# ToF_Bottom.net
KiCad netlist of a schematic drawn in Altium Designer
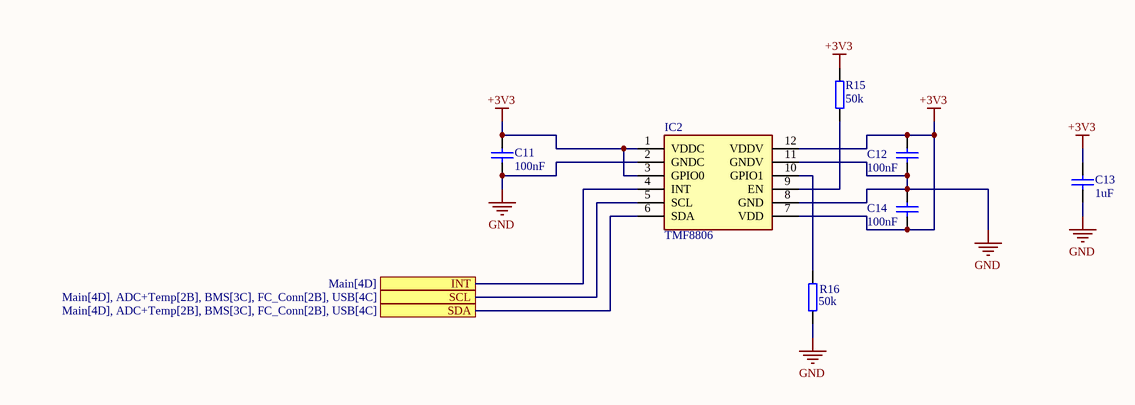
[diagram p0: ToF_Bottom.SchDoc]

(export (version "E")
  (design (tool "Eeschema 10.0.6"))
  (components
    (comp (ref "C11")
      (value "100nF")
      (footprint "CAP0402")
      (fields
        (field (name "VOLTAGE") "50V")
        (field (name "MANUFACTURER_PART_NUMBER") "GRM155R71H104ME14D")
        (field (name "Comment") "Cap0402")
      )
      (libsource (lib "capacitorsSMD") (part "Cap0402"))
    )
    (comp (ref "C12")
      (value "100nF")
      (footprint "CAP0402")
      (fields
        (field (name "VOLTAGE") "50V")
        (field (name "MANUFACTURER_PART_NUMBER") "GRM155R71H104ME14D")
        (field (name "Comment") "Cap0402")
      )
      (libsource (lib "capacitorsSMD") (part "Cap0402"))
    )
    (comp (ref "C13")
      (value "1uF")
      (footprint "CAP0603")
      (fields
        (field (name "VOLTAGE") "25V")
        (field (name "MANUFACTURER_PART_NUMBER") "GRT188R61H105KE13D")
        (field (name "Comment") "Cap0603")
      )
      (libsource (lib "capacitorsSMD") (part "Cap0603"))
    )
    (comp (ref "C14")
      (value "100nF")
      (footprint "CAP0402")
      (fields
        (field (name "VOLTAGE") "50V")
        (field (name "MANUFACTURER_PART_NUMBER") "GRM155R71H104ME14D")
        (field (name "Comment") "Cap0402")
      )
      (libsource (lib "capacitorsSMD") (part "Cap0402"))
    )
    (comp (ref "IC2")
      (value "TMF8806")
      (footprint "SamacSys:TMF88051B")
      (description "Integrated Circuit")
      (fields
        (field (name "MANUFACTURER_PART_NUMBER") "TMF8805-1B")
        (field (name "MOUSER PART NUMBER") "985-TMF8805-1B")
      )
      (libsource (lib "*") (part "TMF8805-1B"))
    )
    (comp (ref "R15")
      (value "50k")
      (footprint "RES0402")
      (fields (field (name "MANUFACTURER_PART_NUMBER") "TNPW040249K9DEED") (field (name "Comment") "Res0402"))
      (libsource (lib "resistorSMD") (part "Res0402"))
    )
    (comp (ref "R16")
      (value "50k")
      (footprint "RES0402")
      (fields (field (name "MANUFACTURER_PART_NUMBER") "TNPW040249K9DEED") (field (name "Comment") "Res0402"))
      (libsource (lib "resistorSMD") (part "Res0402"))
    )
  )
  (nets
    (net (code "1") (name "+3V3") (class "Default")
      (node (ref "C11") (pin "2") (pinfunction "2_2") (pintype "passive"))
      (node (ref "C12") (pin "2") (pinfunction "2_2") (pintype "passive"))
      (node (ref "C13") (pin "2") (pinfunction "2_2") (pintype "passive"))
      (node (ref "C14") (pin "1") (pinfunction "1_1") (pintype "passive"))
      (node (ref "IC2") (pin "1") (pinfunction "VDDC_1") (pintype "passive"))
      (node (ref "IC2") (pin "12") (pinfunction "VDDV_12") (pintype "passive"))
      (node (ref "IC2") (pin "3") (pinfunction "GPIO0_3") (pintype "passive"))
      (node (ref "IC2") (pin "7") (pinfunction "VDD_7") (pintype "passive"))
      (node (ref "R15") (pin "2") (pinfunction "2_2") (pintype "passive"))
    )
    (net (code "2") (name "/INT") (class "Default")
      (node (ref "IC2") (pin "4") (pinfunction "INT_4") (pintype "passive"))
    )
    (net (code "3") (name "/SCL") (class "Default")
      (node (ref "IC2") (pin "5") (pinfunction "SCL_5") (pintype "passive"))
    )
    (net (code "4") (name "/SDA") (class "Default")
      (node (ref "IC2") (pin "6") (pinfunction "SDA_6") (pintype "passive"))
    )
    (net (code "5") (name "GND") (class "Default")
      (node (ref "C11") (pin "1") (pinfunction "1_1") (pintype "passive"))
      (node (ref "C12") (pin "1") (pinfunction "1_1") (pintype "passive"))
      (node (ref "C13") (pin "1") (pinfunction "1_1") (pintype "passive"))
      (node (ref "C14") (pin "2") (pinfunction "2_2") (pintype "passive"))
      (node (ref "IC2") (pin "11") (pinfunction "GNDV_11") (pintype "passive"))
      (node (ref "IC2") (pin "2") (pinfunction "GNDC_2") (pintype "passive"))
      (node (ref "IC2") (pin "8") (pinfunction "GND_8") (pintype "passive"))
      (node (ref "R16") (pin "1") (pinfunction "1_1") (pintype "passive"))
    )
    (net (code "6") (name "Net-(IC2-EN)") (class "Default")
      (node (ref "IC2") (pin "9") (pinfunction "EN_9") (pintype "passive"))
      (node (ref "R15") (pin "1") (pinfunction "1_1") (pintype "passive"))
    )
    (net (code "7") (name "Net-(IC2-GPIO1)") (class "Default")
      (node (ref "IC2") (pin "10") (pinfunction "GPIO1_10") (pintype "passive"))
      (node (ref "R16") (pin "2") (pinfunction "2_2") (pintype "passive"))
    )
  )
)
